# 12V_5V_5A_SchDoc.net
KiCad netlist of a schematic drawn in Altium Designer
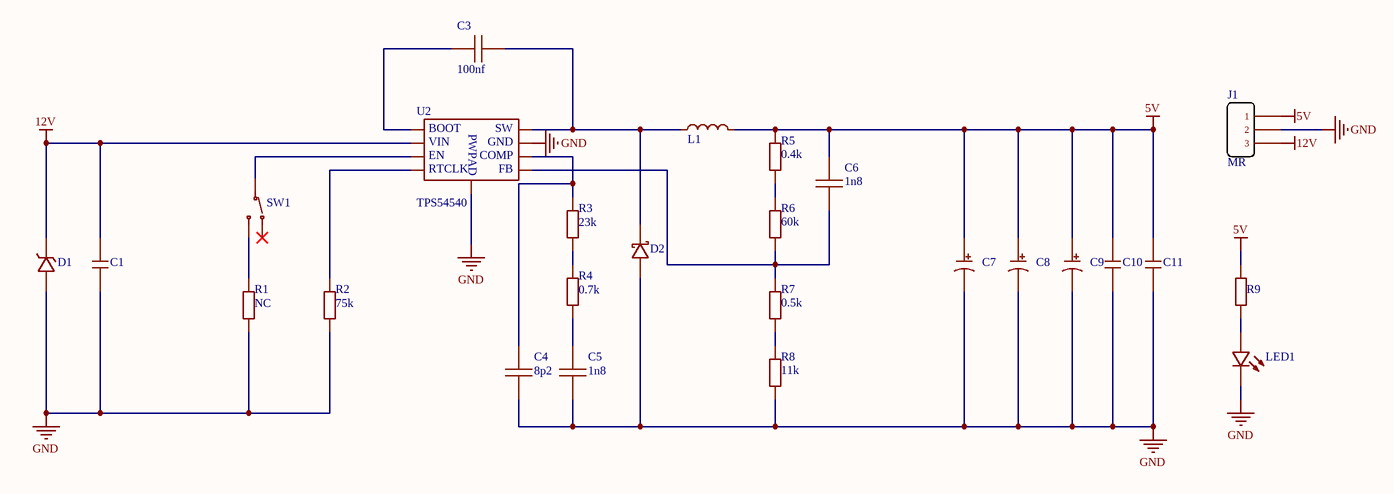
[diagram p0: 12V_5V@5A_SchDoc.SchDoc]

(export (version "E")
  (design (tool "Eeschema 10.0.6"))
  (components
    (comp (ref "C1") (value "10uF") (footprint "0805C") (libsource (lib "") (part "电容_贴片_1")))
    (comp (ref "C3") (value "100nf") (footprint "0603C") (libsource (lib "元件库") (part "电容_贴片")))
    (comp (ref "C4") (value "8p2") (footprint "0603C") (libsource (lib "元件库") (part "电容_贴片")))
    (comp (ref "C5") (value "1n8") (footprint "0603C") (libsource (lib "元件库") (part "电容_贴片")))
    (comp (ref "C6") (value "1n8") (footprint "0603C") (libsource (lib "元件库") (part "电容_贴片")))
    (comp (ref "C7") (value "47uF") (footprint "3528B/1210") (libsource (lib "元件库") (part "电容_贴片钽")))
    (comp (ref "C8") (value "47uF") (footprint "3528B/1210") (libsource (lib "元件库") (part "电容_贴片钽")))
    (comp (ref "C9") (value "47uF") (footprint "3528B/1210") (libsource (lib "元件库") (part "电容_贴片钽")))
    (comp (ref "C10") (value "NC") (footprint "0805C") (libsource (lib "") (part "电容_贴片_1")))
    (comp (ref "C11") (value "100nF") (footprint "0805C") (libsource (lib "") (part "电容_贴片_1")))
    (comp (ref "D1") (value "SMAJ12") (footprint "SMA") (libsource (lib "元件库") (part "二极管_瞬态抑制")))
    (comp (ref "D2") (value "1054") (footprint "TO-277") (libsource (lib "元件库") (part "二极管_肖特基")))
    (comp (ref "J1") (value "MR") (footprint "MR30-FB") (libsource (lib "接口库") (part "接口_MR")))
    (comp (ref "L1") (value "2u2") (footprint "10XXL") (libsource (lib "元件库") (part "电感_贴片")))
    (comp (ref "LED1") (value "LED") (footprint "0603D") (libsource (lib "元件库") (part "二极管_贴片发光")))
    (comp (ref "R1") (value "NC") (footprint "0603R") (libsource (lib "元件库") (part "电阻_贴片")))
    (comp (ref "R2") (value "75k") (footprint "0603R") (libsource (lib "元件库") (part "电阻_贴片")))
    (comp (ref "R3") (value "23k") (footprint "0603R") (libsource (lib "元件库") (part "电阻_贴片")))
    (comp (ref "R4") (value "0.7k") (footprint "0603R") (libsource (lib "元件库") (part "电阻_贴片")))
    (comp (ref "R5") (value "0.4k") (footprint "0603R") (libsource (lib "元件库") (part "电阻_贴片")))
    (comp (ref "R6") (value "60k") (footprint "0603R") (libsource (lib "元件库") (part "电阻_贴片")))
    (comp (ref "R7") (value "0.5k") (footprint "0603R") (libsource (lib "元件库") (part "电阻_贴片")))
    (comp (ref "R8") (value "11k") (footprint "0603R") (libsource (lib "元件库") (part "电阻_贴片")))
    (comp (ref "R9") (value "4K7") (footprint "0603R") (libsource (lib "") (part "电阻_贴片_1")))
    (comp (ref "SW1") (value "开关") (footprint "*SW-1280S") (libsource (lib "元件库") (part "开关_三脚")))
    (comp (ref "U2")
      (value "TPS54540")
      (footprint "SOP-8-PP")
      (libsource (lib "元件库") (part "芯片/IC-TPS54540"))
    )
  )
  (nets
    (net (code "1") (name "5V") (class "Default")
      (node (ref "C10") (pin "1") (pinfunction "1_1") (pintype "passive"))
      (node (ref "C11") (pin "1") (pinfunction "1_1") (pintype "passive"))
      (node (ref "C6") (pin "2") (pinfunction "2_2") (pintype "passive"))
      (node (ref "C7") (pin "1") (pinfunction "1_1") (pintype "passive"))
      (node (ref "C8") (pin "1") (pinfunction "1_1") (pintype "passive"))
      (node (ref "C9") (pin "1") (pinfunction "1_1") (pintype "passive"))
      (node (ref "J1") (pin "1") (pinfunction "1_1") (pintype "passive"))
      (node (ref "L1") (pin "2") (pinfunction "2_2") (pintype "passive"))
      (node (ref "R5") (pin "2") (pinfunction "2_2") (pintype "passive"))
      (node (ref "R9") (pin "1") (pinfunction "1_1") (pintype "passive"))
    )
    (net (code "2") (name "12V") (class "Default")
      (node (ref "C1") (pin "1") (pinfunction "1_1") (pintype "passive"))
      (node (ref "D1") (pin "2") (pinfunction "2_2") (pintype "passive"))
      (node (ref "J1") (pin "3") (pinfunction "3_3") (pintype "passive"))
      (node (ref "U2") (pin "2") (pinfunction "2_2") (pintype "passive"))
    )
    (net (code "3") (name "GND") (class "Default")
      (node (ref "C1") (pin "2") (pinfunction "2_2") (pintype "passive"))
      (node (ref "C10") (pin "2") (pinfunction "2_2") (pintype "passive"))
      (node (ref "C11") (pin "2") (pinfunction "2_2") (pintype "passive"))
      (node (ref "C4") (pin "2") (pinfunction "2_2") (pintype "passive"))
      (node (ref "C5") (pin "2") (pinfunction "2_2") (pintype "passive"))
      (node (ref "C7") (pin "2") (pinfunction "2_2") (pintype "passive"))
      (node (ref "C8") (pin "2") (pinfunction "2_2") (pintype "passive"))
      (node (ref "C9") (pin "2") (pinfunction "2_2") (pintype "passive"))
      (node (ref "D1") (pin "1") (pinfunction "1_1") (pintype "passive"))
      (node (ref "D2") (pin "1") (pinfunction "1_1") (pintype "passive"))
      (node (ref "J1") (pin "2") (pinfunction "2_2") (pintype "passive"))
      (node (ref "LED1") (pin "2") (pinfunction "2_2") (pintype "passive"))
      (node (ref "R1") (pin "1") (pinfunction "1_1") (pintype "passive"))
      (node (ref "R2") (pin "1") (pinfunction "1_1") (pintype "passive"))
      (node (ref "R8") (pin "1") (pinfunction "1_1") (pintype "passive"))
      (node (ref "U2") (pin "7") (pinfunction "7_7") (pintype "passive"))
      (node (ref "U2") (pin "9") (pinfunction "9_9") (pintype "passive"))
    )
    (net (code "4") (name "Net-(C3-Pad1)") (class "Default")
      (node (ref "C3") (pin "1") (pinfunction "1_1") (pintype "passive"))
      (node (ref "U2") (pin "1") (pinfunction "1_1") (pintype "passive"))
    )
    (net (code "5") (name "Net-(C3-Pad2)") (class "Default")
      (node (ref "C3") (pin "2") (pinfunction "2_2") (pintype "passive"))
      (node (ref "D2") (pin "2") (pinfunction "2_2") (pintype "passive"))
      (node (ref "L1") (pin "1") (pinfunction "1_1") (pintype "passive"))
      (node (ref "U2") (pin "8") (pinfunction "8_8") (pintype "passive"))
    )
    (net (code "6") (name "Net-(C4-Pad1)") (class "Default")
      (node (ref "C4") (pin "1") (pinfunction "1_1") (pintype "passive"))
      (node (ref "R3") (pin "2") (pinfunction "2_2") (pintype "passive"))
      (node (ref "U2") (pin "6") (pinfunction "6_6") (pintype "passive"))
    )
    (net (code "7") (name "Net-(C5-Pad1)") (class "Default")
      (node (ref "C5") (pin "1") (pinfunction "1_1") (pintype "passive"))
      (node (ref "R4") (pin "1") (pinfunction "1_1") (pintype "passive"))
    )
    (net (code "8") (name "Net-(C6-Pad1)") (class "Default")
      (node (ref "C6") (pin "1") (pinfunction "1_1") (pintype "passive"))
      (node (ref "R6") (pin "1") (pinfunction "1_1") (pintype "passive"))
      (node (ref "R7") (pin "2") (pinfunction "2_2") (pintype "passive"))
      (node (ref "U2") (pin "5") (pinfunction "5_5") (pintype "passive"))
    )
    (net (code "9") (name "Net-(LED1-Pad1)") (class "Default")
      (node (ref "LED1") (pin "1") (pinfunction "1_1") (pintype "passive"))
      (node (ref "R9") (pin "2") (pinfunction "2_2") (pintype "passive"))
    )
    (net (code "10") (name "Net-(R1-Pad2)") (class "Default")
      (node (ref "R1") (pin "2") (pinfunction "2_2") (pintype "passive"))
      (node (ref "SW1") (pin "3") (pinfunction "3_3") (pintype "passive"))
    )
    (net (code "11") (name "Net-(R2-Pad2)") (class "Default")
      (node (ref "R2") (pin "2") (pinfunction "2_2") (pintype "passive"))
      (node (ref "U2") (pin "4") (pinfunction "4_4") (pintype "passive"))
    )
    (net (code "12") (name "Net-(R3-Pad1)") (class "Default")
      (node (ref "R3") (pin "1") (pinfunction "1_1") (pintype "passive"))
      (node (ref "R4") (pin "2") (pinfunction "2_2") (pintype "passive"))
    )
    (net (code "13") (name "Net-(R5-Pad1)") (class "Default")
      (node (ref "R5") (pin "1") (pinfunction "1_1") (pintype "passive"))
      (node (ref "R6") (pin "2") (pinfunction "2_2") (pintype "passive"))
    )
    (net (code "14") (name "Net-(R7-Pad1)") (class "Default")
      (node (ref "R7") (pin "1") (pinfunction "1_1") (pintype "passive"))
      (node (ref "R8") (pin "2") (pinfunction "2_2") (pintype "passive"))
    )
    (net (code "15") (name "Net-(SW1-Pad1)") (class "Default")
      (node (ref "SW1") (pin "1") (pinfunction "1_1") (pintype "passive"))
      (node (ref "U2") (pin "3") (pinfunction "3_3") (pintype "passive"))
    )
    (net (code "16") (name "unconnected-(SW1-Pad2)") (class "Default")
      (node (ref "SW1") (pin "2") (pinfunction "2_2") (pintype "passive+no_connect"))
    )
  )
)
